# first_design.net
KiCad netlist of a schematic drawn in EAGLE
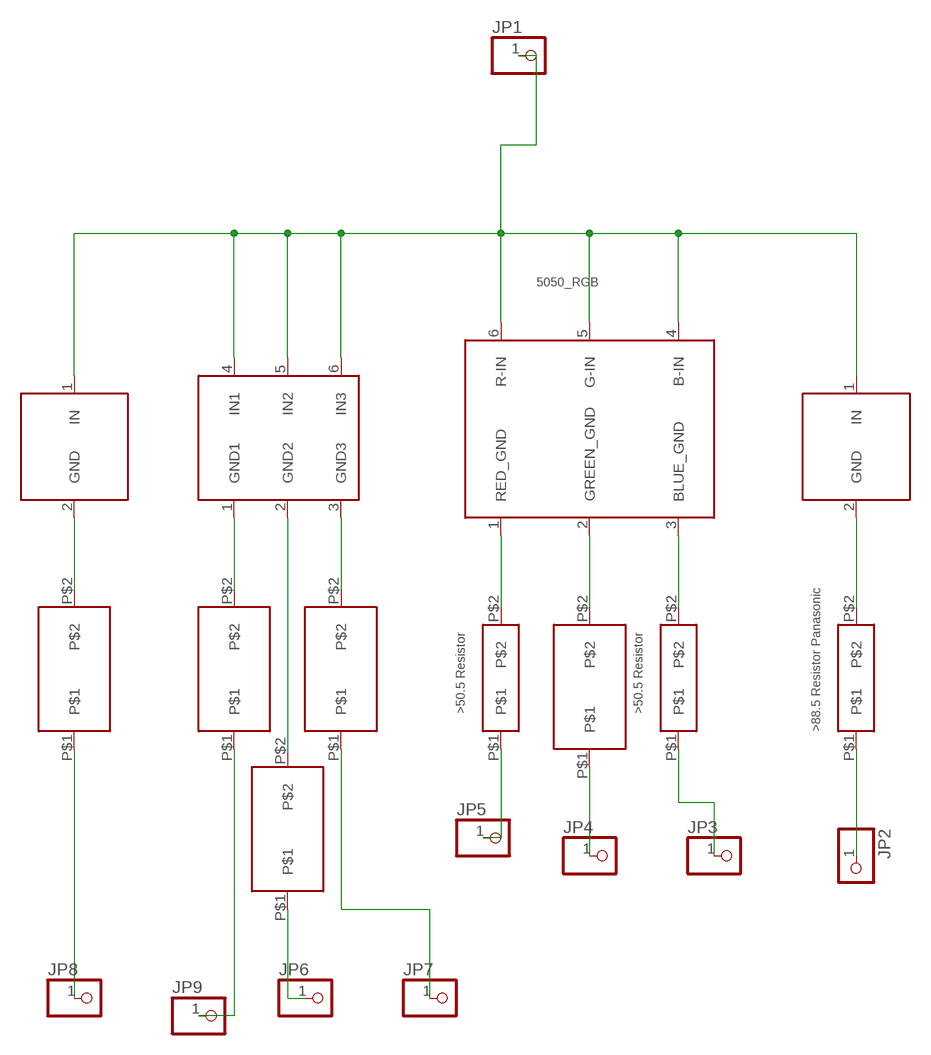
[diagram p0: schematic, sheet 1]

(export (version "E")
  (design (tool "Eeschema 10.0.6"))
  (components
    (comp (ref "JP1")
      (value "PINHD-1X1")
      (footprint "eagle-import:1X01")
      (libsource (lib "eagle-import") (part "PINHD-1X1"))
    )
    (comp (ref "JP2")
      (value "PINHD-1X1")
      (footprint "eagle-import:1X01")
      (libsource (lib "eagle-import") (part "PINHD-1X1"))
    )
    (comp (ref "JP3")
      (value "PINHD-1X1")
      (footprint "eagle-import:1X01")
      (libsource (lib "eagle-import") (part "PINHD-1X1"))
    )
    (comp (ref "JP4")
      (value "PINHD-1X1")
      (footprint "eagle-import:1X01")
      (libsource (lib "eagle-import") (part "PINHD-1X1"))
    )
    (comp (ref "JP5")
      (value "PINHD-1X1")
      (footprint "eagle-import:1X01")
      (libsource (lib "eagle-import") (part "PINHD-1X1"))
    )
    (comp (ref "JP6")
      (value "PINHD-1X1")
      (footprint "eagle-import:1X01")
      (libsource (lib "eagle-import") (part "PINHD-1X1"))
    )
    (comp (ref "JP7")
      (value "PINHD-1X1")
      (footprint "eagle-import:1X01")
      (libsource (lib "eagle-import") (part "PINHD-1X1"))
    )
    (comp (ref "JP8")
      (value "PINHD-1X1")
      (footprint "eagle-import:1X01")
      (libsource (lib "eagle-import") (part "PINHD-1X1"))
    )
    (comp (ref "JP9")
      (value "PINHD-1X1")
      (footprint "eagle-import:1X01")
      (libsource (lib "eagle-import") (part "PINHD-1X1"))
    )
    (comp (ref "U$1")
      (value "5.0X5.0_WHITE_LED")
      (footprint "eagle-import:COOLWHITE5050LED")
      (libsource (lib "eagle-import") (part "5.0X5.0_WHITE_LED"))
    )
    (comp (ref "U$2")
      (value "5050_RGB_LED")
      (footprint "eagle-import:RGB5050LED")
      (libsource (lib "eagle-import") (part "5050_RGB_LED"))
    )
    (comp (ref "U$3")
      (value "IR_LED")
      (footprint "eagle-import:IR_LED")
      (libsource (lib "eagle-import") (part "IR_LED"))
    )
    (comp (ref "U$4")
      (value "UV_LED")
      (footprint "eagle-import:UV_LED")
      (libsource (lib "eagle-import") (part "UV_LED"))
    )
    (comp (ref "U$5")
      (value "88.5_RESISTOR_PANASONIC")
      (footprint "eagle-import:88.7_RESISTOR_PANASONIC")
      (libsource (lib "eagle-import") (part "88.5_RESISTOR_PANASONIC"))
    )
    (comp (ref "U$6")
      (value "68_60_56_RESISTOR_VISHAY")
      (footprint "eagle-import:68_60_56_RESISTOR_VISHAY")
      (libsource (lib "eagle-import") (part "68_60_56_RESISTOR_VISHAY"))
    )
    (comp (ref "U$7")
      (value "68_60_56_RESISTOR_VISHAY")
      (footprint "eagle-import:68_60_56_RESISTOR_VISHAY")
      (libsource (lib "eagle-import") (part "68_60_56_RESISTOR_VISHAY"))
    )
    (comp (ref "U$8")
      (value "68_60_56_RESISTOR_VISHAY")
      (footprint "eagle-import:68_60_56_RESISTOR_VISHAY")
      (libsource (lib "eagle-import") (part "68_60_56_RESISTOR_VISHAY"))
    )
    (comp (ref "U$9")
      (value "68_60_56_RESISTOR_VISHAY")
      (footprint "eagle-import:68_60_56_RESISTOR_VISHAY")
      (libsource (lib "eagle-import") (part "68_60_56_RESISTOR_VISHAY"))
    )
    (comp (ref "U$10")
      (value "50.5_RESISTOR_TT")
      (footprint "eagle-import:50.5_RESISTOR_TT")
      (libsource (lib "eagle-import") (part "50.5_RESISTOR_TT"))
    )
    (comp (ref "U$11")
      (value "50.5_RESISTOR_TT")
      (footprint "eagle-import:50.5_RESISTOR_TT")
      (libsource (lib "eagle-import") (part "50.5_RESISTOR_TT"))
    )
    (comp (ref "U$12")
      (value "68_60_56_RESISTOR_VISHAY")
      (footprint "eagle-import:68_60_56_RESISTOR_VISHAY")
      (libsource (lib "eagle-import") (part "68_60_56_RESISTOR_VISHAY"))
    )
  )
  (nets
    (net (code "1") (name "Net-(JP2-Pad1)") (class "Default")
      (node (ref "JP2") (pin "1") (pinfunction "1_1") (pintype "passive"))
      (node (ref "U$5") (pin "P$1") (pinfunction "P$1_P$1") (pintype "bidirectional"))
    )
    (net (code "2") (name "Net-(JP3-Pad1)") (class "Default")
      (node (ref "JP3") (pin "1") (pinfunction "1_1") (pintype "passive"))
      (node (ref "U$11") (pin "P$1") (pinfunction "P$1_P$1") (pintype "bidirectional"))
    )
    (net (code "3") (name "Net-(JP4-Pad1)") (class "Default")
      (node (ref "JP4") (pin "1") (pinfunction "1_1") (pintype "passive"))
      (node (ref "U$12") (pin "P$1") (pinfunction "P$1_P$1") (pintype "bidirectional"))
    )
    (net (code "4") (name "Net-(JP5-Pad1)") (class "Default")
      (node (ref "JP5") (pin "1") (pinfunction "1_1") (pintype "passive"))
      (node (ref "U$10") (pin "P$1") (pinfunction "P$1_P$1") (pintype "bidirectional"))
    )
    (net (code "5") (name "Net-(JP6-Pad1)") (class "Default")
      (node (ref "JP6") (pin "1") (pinfunction "1_1") (pintype "passive"))
      (node (ref "U$8") (pin "P$1") (pinfunction "P$1_P$1") (pintype "bidirectional"))
    )
    (net (code "6") (name "Net-(JP7-Pad1)") (class "Default")
      (node (ref "JP7") (pin "1") (pinfunction "1_1") (pintype "passive"))
      (node (ref "U$9") (pin "P$1") (pinfunction "P$1_P$1") (pintype "bidirectional"))
    )
    (net (code "7") (name "Net-(JP8-Pad1)") (class "Default")
      (node (ref "JP8") (pin "1") (pinfunction "1_1") (pintype "passive"))
      (node (ref "U$6") (pin "P$1") (pinfunction "P$1_P$1") (pintype "bidirectional"))
    )
    (net (code "8") (name "Net-(JP9-Pad1)") (class "Default")
      (node (ref "JP9") (pin "1") (pinfunction "1_1") (pintype "passive"))
      (node (ref "U$7") (pin "P$1") (pinfunction "P$1_P$1") (pintype "bidirectional"))
    )
    (net (code "9") (name "Net-(U$1-GND1)") (class "Default")
      (node (ref "U$1") (pin "1") (pinfunction "GND1_1") (pintype "bidirectional"))
      (node (ref "U$7") (pin "P$2") (pinfunction "P$2_P$2") (pintype "bidirectional"))
    )
    (net (code "10") (name "Net-(U$1-GND2)") (class "Default")
      (node (ref "U$1") (pin "2") (pinfunction "GND2_2") (pintype "bidirectional"))
      (node (ref "U$8") (pin "P$2") (pinfunction "P$2_P$2") (pintype "bidirectional"))
    )
    (net (code "11") (name "Net-(U$1-GND3)") (class "Default")
      (node (ref "U$1") (pin "3") (pinfunction "GND3_3") (pintype "bidirectional"))
      (node (ref "U$9") (pin "P$2") (pinfunction "P$2_P$2") (pintype "bidirectional"))
    )
    (net (code "12") (name "Net-(U$1-IN1)") (class "Default")
      (node (ref "JP1") (pin "1") (pinfunction "1_1") (pintype "passive"))
      (node (ref "U$1") (pin "4") (pinfunction "IN1_4") (pintype "bidirectional"))
      (node (ref "U$1") (pin "5") (pinfunction "IN2_5") (pintype "bidirectional"))
      (node (ref "U$1") (pin "6") (pinfunction "IN3_6") (pintype "bidirectional"))
      (node (ref "U$2") (pin "4") (pinfunction "B-IN_4") (pintype "bidirectional"))
      (node (ref "U$2") (pin "5") (pinfunction "G-IN_5") (pintype "bidirectional"))
      (node (ref "U$2") (pin "6") (pinfunction "R-IN_6") (pintype "bidirectional"))
      (node (ref "U$3") (pin "1") (pinfunction "IN_1") (pintype "bidirectional"))
      (node (ref "U$4") (pin "1") (pinfunction "IN_1") (pintype "bidirectional"))
    )
    (net (code "13") (name "Net-(U$2-BLUE_GND)") (class "Default")
      (node (ref "U$11") (pin "P$2") (pinfunction "P$2_P$2") (pintype "bidirectional"))
      (node (ref "U$2") (pin "3") (pinfunction "BLUE_GND_3") (pintype "bidirectional"))
    )
    (net (code "14") (name "Net-(U$2-GREEN_GND)") (class "Default")
      (node (ref "U$12") (pin "P$2") (pinfunction "P$2_P$2") (pintype "bidirectional"))
      (node (ref "U$2") (pin "2") (pinfunction "GREEN_GND_2") (pintype "bidirectional"))
    )
    (net (code "15") (name "Net-(U$2-RED_GND)") (class "Default")
      (node (ref "U$10") (pin "P$2") (pinfunction "P$2_P$2") (pintype "bidirectional"))
      (node (ref "U$2") (pin "1") (pinfunction "RED_GND_1") (pintype "bidirectional"))
    )
    (net (code "16") (name "Net-(U$3-GND)") (class "Default")
      (node (ref "U$3") (pin "2") (pinfunction "GND_2") (pintype "bidirectional"))
      (node (ref "U$6") (pin "P$2") (pinfunction "P$2_P$2") (pintype "bidirectional"))
    )
    (net (code "17") (name "Net-(U$4-GND)") (class "Default")
      (node (ref "U$4") (pin "2") (pinfunction "GND_2") (pintype "bidirectional"))
      (node (ref "U$5") (pin "P$2") (pinfunction "P$2_P$2") (pintype "bidirectional"))
    )
  )
)
